# turn_on_delay.net
KiCad netlist of a schematic drawn in Altium Designer
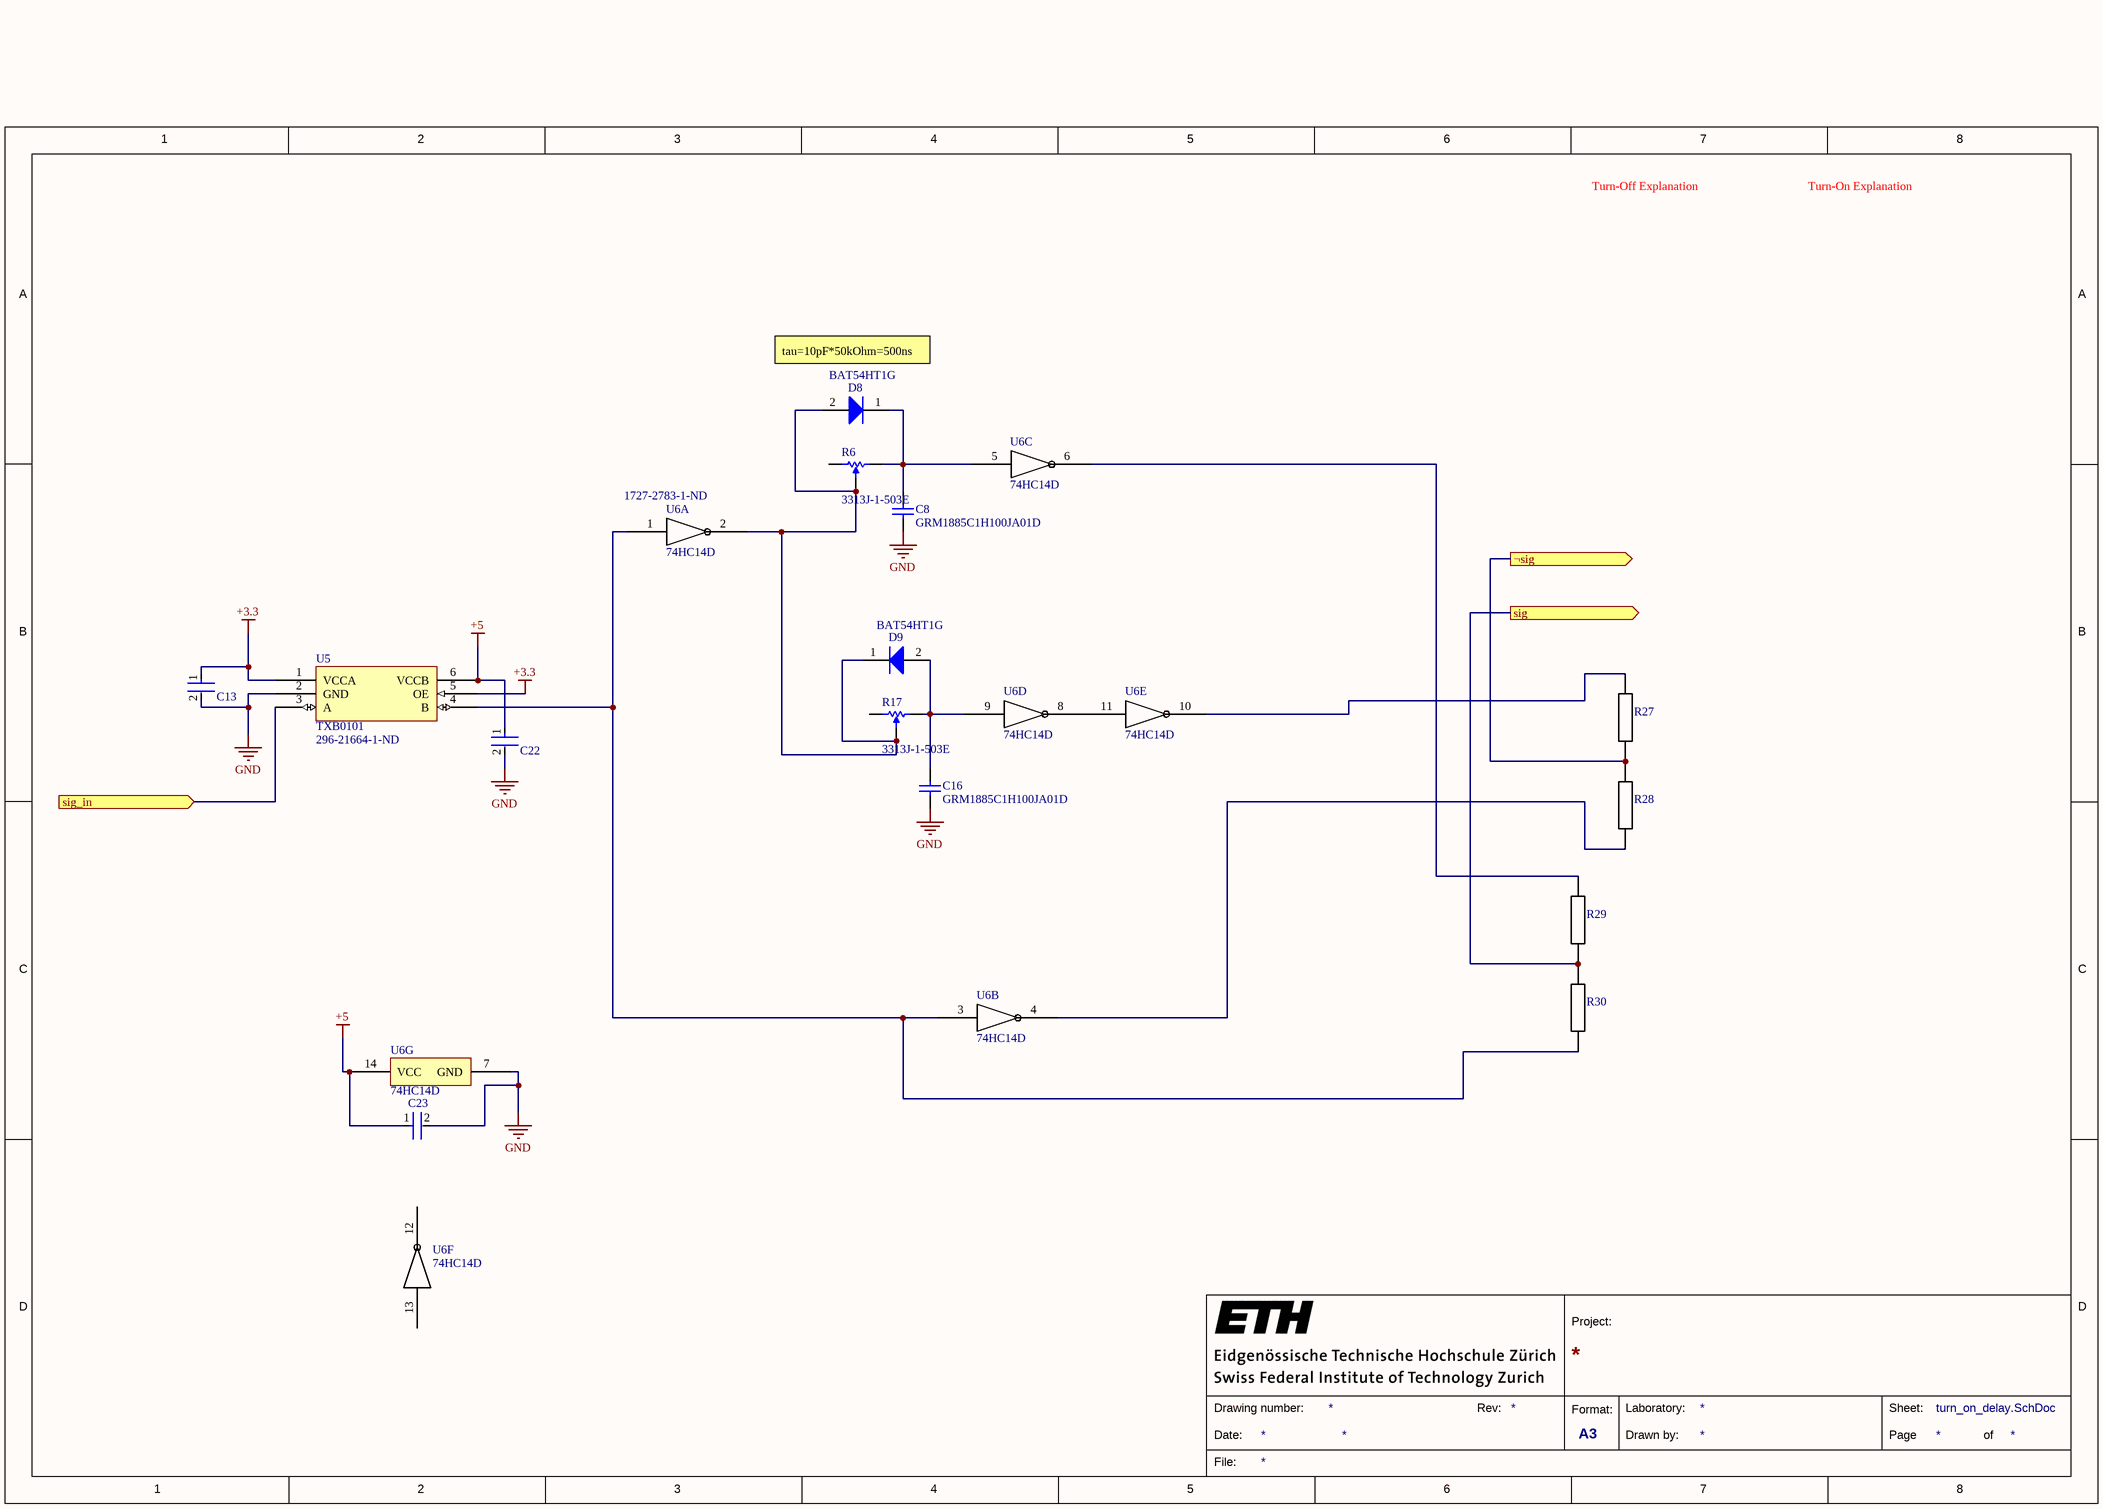
[diagram p0: turn_on_delay.SchDoc]

(export (version "E")
  (design (tool "Eeschema 10.0.6"))
  (components
    (comp (ref "C8")
      (value "GRM1885C1H100JA01D")
      (footprint "CAPC1608X90X35LL10T15")
      (fields (field (name "MANUFACTURER") "Murata"))
      (libsource (lib "Altium Content Vault") (part "CAP"))
    )
    (comp (ref "C13")
      (value "C0603X104K5RACTU")
      (footprint "FP-C0603-CJ-MFG")
      (description "CAP CER 0.1UF 50V X7R 0603")
      (fields (field (name "VOLTAGE") "50V") (field (name "MANUFACTURER") "Kemet"))
      (libsource (lib "Altium Content Vault") (part "11868f565c42a9108669ba33697ecf6"))
    )
    (comp (ref "C16")
      (value "GRM1885C1H100JA01D")
      (footprint "CAPC1608X90X35LL10T15")
      (fields (field (name "MANUFACTURER") "Murata"))
      (libsource (lib "Altium Content Vault") (part "CAP"))
    )
    (comp (ref "C22")
      (value "C0603X104K5RACTU")
      (footprint "FP-C0603-CJ-MFG")
      (description "CAP CER 0.1UF 50V X7R 0603")
      (fields (field (name "VOLTAGE") "50V") (field (name "MANUFACTURER") "Kemet"))
      (libsource (lib "Altium Content Vault") (part "11868f565c42a9108669ba33697ecf6"))
    )
    (comp (ref "C23")
      (value "C0603X104K5RACTU")
      (footprint "FP-C0603-CJ-MFG")
      (description "CAP CER 0.1UF 50V X7R 0603")
      (fields (field (name "VOLTAGE") "50V") (field (name "MANUFACTURER") "Kemet"))
      (libsource (lib "Altium Content Vault") (part "11868f565c42a9108669ba33697ecf6"))
    )
    (comp (ref "D8")
      (value "BAT54HT1G")
      (footprint "ONSC-SOD-323-2-477-02_V")
      (description "Schottky Barrier Diode, 2-Pin SOD-323, Pb-Free, Tape and Reel")
      (fields (field (name "MANUFACTURER") "On Semiconductor"))
      (libsource (lib "Altium Content Vault") (part "ONSC-D-K1A2-2"))
    )
    (comp (ref "D9")
      (value "BAT54HT1G")
      (footprint "ONSC-SOD-323-2-477-02_V")
      (description "Schottky Barrier Diode, 2-Pin SOD-323, Pb-Free, Tape and Reel")
      (fields (field (name "MANUFACTURER") "On Semiconductor"))
      (libsource (lib "Altium Content Vault") (part "ONSC-D-K1A2-2"))
    )
    (comp (ref "R6")
      (value "3313J-1-503E")
      (footprint "BOUR-3313J-1_V")
      (fields (field (name "MANUFACTURER") "Bourns"))
      (libsource (lib "Altium Content Vault") (part "RES-ADJ-3_A"))
    )
    (comp (ref "R17")
      (value "3313J-1-503E")
      (footprint "BOUR-3313J-1_V")
      (fields (field (name "MANUFACTURER") "Bourns"))
      (libsource (lib "Altium Content Vault") (part "RES-ADJ-3_A"))
    )
    (comp (ref "R27")
      (value "res_smd")
      (footprint "0805")
      (libsource (lib "coil_driver_lib") (part "res_smd"))
    )
    (comp (ref "R28")
      (value "res_smd")
      (footprint "0805")
      (libsource (lib "coil_driver_lib") (part "res_smd"))
    )
    (comp (ref "R29")
      (value "res_smd")
      (footprint "0805")
      (libsource (lib "coil_driver_lib") (part "res_smd"))
    )
    (comp (ref "R30")
      (value "res_smd")
      (footprint "0805")
      (libsource (lib "coil_driver_lib") (part "res_smd"))
    )
    (comp (ref "U5")
      (value "TXB0101")
      (footprint "SOT-23-6")
      (description "Level Shift IC [1.2V...3.6V] -> [1.65V...5.5V]")
      (fields (field (name "SUPPLIER PART NUMBER 1") "296-21664-1-ND"))
      (libsource (lib "coil_driver_lib") (part "TXB0101"))
    )
    (comp (ref "U6")
      (value "74HC14D")
      (footprint "SOP14_narrow")
      (fields (field (name "SUPPLIER PART NUMBER 1") "1727-2783-1-ND"))
      (libsource (lib "coil_driver_lib") (part "74HC14D"))
    )
  )
  (nets
    (net (code "1") (name "+3.3") (class "Default")
      (node (ref "C13") (pin "1") (pinfunction "1_1") (pintype "passive"))
      (node (ref "U5") (pin "1") (pinfunction "VCCA_1") (pintype "power_in"))
      (node (ref "U5") (pin "5") (pinfunction "OE_5") (pintype "input"))
    )
    (net (code "2") (name "+5") (class "Default")
      (node (ref "C22") (pin "1") (pinfunction "1_1") (pintype "passive"))
      (node (ref "C23") (pin "1") (pinfunction "1_1") (pintype "passive"))
      (node (ref "U5") (pin "6") (pinfunction "VCCB_6") (pintype "power_in"))
      (node (ref "U6") (pin "14") (pinfunction "VCC_14") (pintype "passive"))
    )
    (net (code "3") (name "/sig") (class "Default")
      (node (ref "R29") (pin "2") (pinfunction "2_2") (pintype "passive"))
      (node (ref "R30") (pin "1") (pinfunction "1_1") (pintype "passive"))
    )
    (net (code "4") (name "/sig_in") (class "Default")
      (node (ref "U5") (pin "3") (pinfunction "A_3") (pintype "bidirectional"))
    )
    (net (code "5") (name "/¬sig") (class "Default")
      (node (ref "R27") (pin "2") (pinfunction "2_2") (pintype "passive"))
      (node (ref "R28") (pin "1") (pinfunction "1_1") (pintype "passive"))
    )
    (net (code "6") (name "GND") (class "Default")
      (node (ref "C13") (pin "2") (pinfunction "2_2") (pintype "passive"))
      (node (ref "C16") (pin "1") (pinfunction "1_1") (pintype "passive"))
      (node (ref "C22") (pin "2") (pinfunction "2_2") (pintype "passive"))
      (node (ref "C23") (pin "2") (pinfunction "2_2") (pintype "passive"))
      (node (ref "C8") (pin "1") (pinfunction "1_1") (pintype "passive"))
      (node (ref "U5") (pin "2") (pinfunction "GND_2") (pintype "power_in"))
      (node (ref "U6") (pin "7") (pinfunction "GND_7") (pintype "passive"))
    )
    (net (code "7") (name "Net-(D8-A)") (class "Default")
      (node (ref "D8") (pin "2") (pinfunction "A_2") (pintype "passive"))
      (node (ref "D9") (pin "1") (pinfunction "K_1") (pintype "passive"))
      (node (ref "R17") (pin "2") (pinfunction "2_2") (pintype "passive"))
      (node (ref "R6") (pin "2") (pinfunction "2_2") (pintype "passive"))
      (node (ref "U6") (pin "2") (pinfunction "1Y_2") (pintype "passive"))
    )
    (net (code "8") (name "Net-(D8-K)") (class "Default")
      (node (ref "C8") (pin "2") (pinfunction "2_2") (pintype "passive"))
      (node (ref "D8") (pin "1") (pinfunction "K_1") (pintype "passive"))
      (node (ref "R6") (pin "3") (pinfunction "3_3") (pintype "passive"))
      (node (ref "U6") (pin "5") (pinfunction "3A_5") (pintype "passive"))
    )
    (net (code "9") (name "Net-(D9-A)") (class "Default")
      (node (ref "C16") (pin "2") (pinfunction "2_2") (pintype "passive"))
      (node (ref "D9") (pin "2") (pinfunction "A_2") (pintype "passive"))
      (node (ref "R17") (pin "3") (pinfunction "3_3") (pintype "passive"))
      (node (ref "U6") (pin "9") (pinfunction "4A_9") (pintype "passive"))
    )
    (net (code "10") (name "Net-(U5-B)") (class "Default")
      (node (ref "R30") (pin "2") (pinfunction "2_2") (pintype "passive"))
      (node (ref "U5") (pin "4") (pinfunction "B_4") (pintype "bidirectional"))
      (node (ref "U6") (pin "1") (pinfunction "1A_1") (pintype "passive"))
      (node (ref "U6") (pin "3") (pinfunction "2A_3") (pintype "passive"))
    )
    (net (code "11") (name "Net-(U6B-2Y)") (class "Default")
      (node (ref "R28") (pin "2") (pinfunction "2_2") (pintype "passive"))
      (node (ref "U6") (pin "4") (pinfunction "2Y_4") (pintype "passive"))
    )
    (net (code "12") (name "Net-(U6C-3Y)") (class "Default")
      (node (ref "R29") (pin "1") (pinfunction "1_1") (pintype "passive"))
      (node (ref "U6") (pin "6") (pinfunction "3Y_6") (pintype "passive"))
    )
    (net (code "13") (name "Net-(U6D-4Y)") (class "Default")
      (node (ref "U6") (pin "11") (pinfunction "5A_11") (pintype "passive"))
      (node (ref "U6") (pin "8") (pinfunction "4Y_8") (pintype "passive"))
    )
    (net (code "14") (name "Net-(U6E-5Y)") (class "Default")
      (node (ref "R27") (pin "1") (pinfunction "1_1") (pintype "passive"))
      (node (ref "U6") (pin "10") (pinfunction "5Y_10") (pintype "passive"))
    )
    (net (code "15") (name "unconnected-(R6-Pad1)") (class "Default")
      (node (ref "R6") (pin "1") (pinfunction "1_1") (pintype "passive"))
    )
    (net (code "16") (name "unconnected-(R17-Pad1)") (class "Default")
      (node (ref "R17") (pin "1") (pinfunction "1_1") (pintype "passive"))
    )
    (net (code "17") (name "unconnected-(U6F-6A-Pad13)") (class "Default")
      (node (ref "U6") (pin "13") (pinfunction "6A_13") (pintype "passive"))
    )
    (net (code "18") (name "unconnected-(U6F-6Y-Pad12)") (class "Default")
      (node (ref "U6") (pin "12") (pinfunction "6Y_12") (pintype "passive"))
    )
  )
)
